# psxpwr.net
KiCad netlist of a schematic drawn in EAGLE
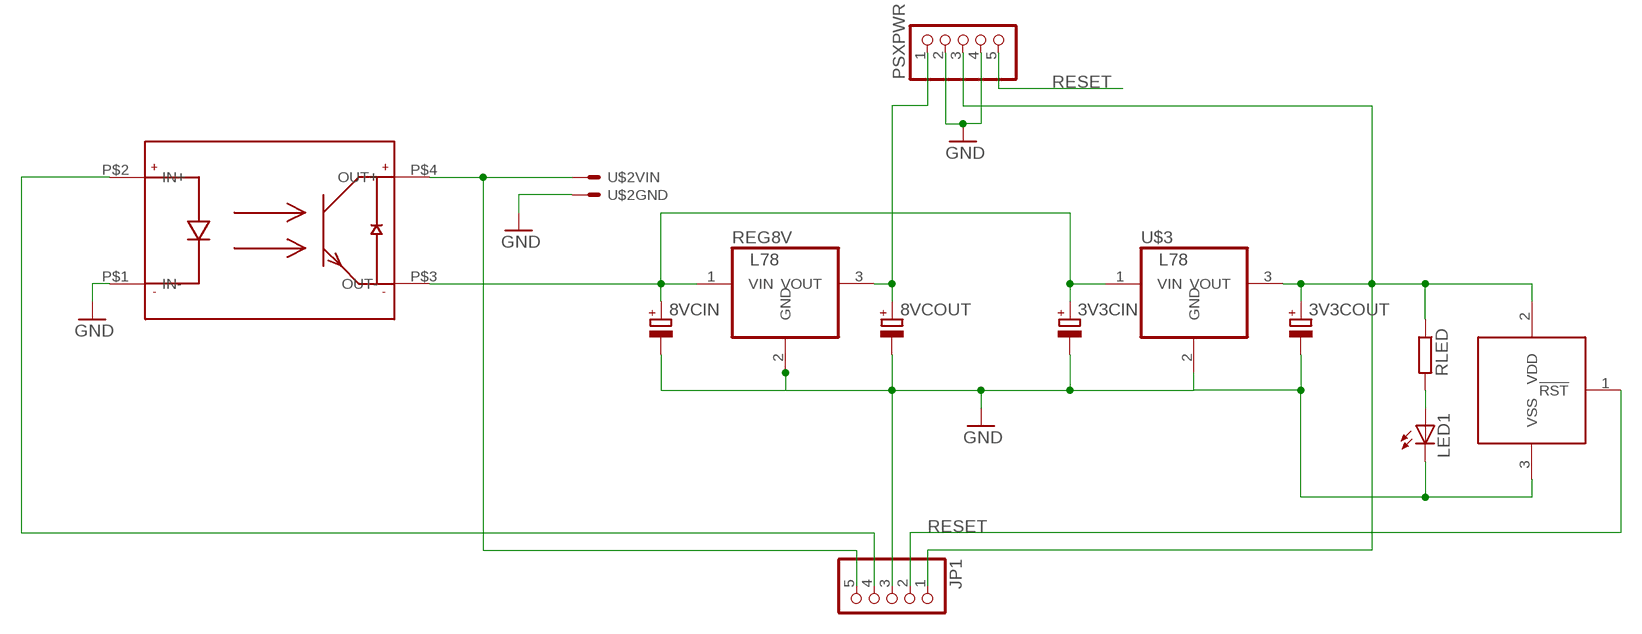
[diagram p0: schematic, sheet 1]

(export (version "E")
  (design (tool "Eeschema 10.0.6"))
  (components
    (comp (ref "3V3CIN")
      (value "CPOL-EUE2.5-6")
      (footprint "eagle-import:E2,5-6")
      (libsource (lib "eagle-import") (part "CPOL-EUE2.5-6"))
    )
    (comp (ref "3V3COUT")
      (value "CPOL-EUE2.5-6")
      (footprint "eagle-import:E2,5-6")
      (libsource (lib "eagle-import") (part "CPOL-EUE2.5-6"))
    )
    (comp (ref "8VCIN")
      (value "CPOL-EUE2.5-6")
      (footprint "eagle-import:E2,5-6")
      (libsource (lib "eagle-import") (part "CPOL-EUE2.5-6"))
    )
    (comp (ref "8VCOUT")
      (value "CPOL-EUE2.5-6")
      (footprint "eagle-import:E2,5-6")
      (libsource (lib "eagle-import") (part "CPOL-EUE2.5-6"))
    )
    (comp (ref "JP1")
      (value "PINHD-1X5")
      (footprint "eagle-import:1X05")
      (libsource (lib "eagle-import") (part "PINHD-1X5"))
    )
    (comp (ref "LED1")
      (value "LED3MM")
      (footprint "eagle-import:LED3MM")
      (libsource (lib "eagle-import") (part "LED3MM"))
    )
    (comp (ref "PSXPWR")
      (value "PINHD-1X5")
      (footprint "eagle-import:1X05")
      (libsource (lib "eagle-import") (part "PINHD-1X5"))
    )
    (comp (ref "REG8V")
      (value "L78")
      (footprint "eagle-import:TO-220-HEATSINK")
      (libsource (lib "eagle-import") (part "L78"))
    )
    (comp (ref "RESET")
      (value "MCP100V3")
      (footprint "eagle-import:TO92-EBC-OVAL")
      (libsource (lib "eagle-import") (part "MCP100V3"))
    )
    (comp (ref "RLED")
      (value "R-EU_0207/2V")
      (footprint "eagle-import:0207_2V")
      (libsource (lib "eagle-import") (part "R-EU_0207/2V"))
    )
    (comp (ref "U$1")
      (value "KF060XD")
      (footprint "eagle-import:KF060XD")
      (libsource (lib "eagle-import") (part "KF060XD"))
    )
    (comp (ref "U$2")
      (value "PWR")
      (footprint "eagle-import:PWR")
      (libsource (lib "eagle-import") (part "PWR"))
    )
    (comp (ref "U$3")
      (value "L78")
      (footprint "eagle-import:TO-220-HEATSINK")
      (libsource (lib "eagle-import") (part "L78"))
    )
  )
  (nets
    (net (code "1") (name "/RESET") (class "Default")
      (node (ref "JP1") (pin "2") (pinfunction "2_2") (pintype "passive"))
      (node (ref "PSXPWR") (pin "5") (pinfunction "5_5") (pintype "passive"))
      (node (ref "RESET") (pin "1") (pinfunction "~{RST}_1") (pintype "bidirectional"))
    )
    (net (code "2") (name "GND") (class "Default")
      (node (ref "3V3CIN") (pin "-") (pinfunction "-_-") (pintype "passive"))
      (node (ref "3V3COUT") (pin "-") (pinfunction "-_-") (pintype "passive"))
      (node (ref "8VCIN") (pin "-") (pinfunction "-_-") (pintype "passive"))
      (node (ref "8VCOUT") (pin "-") (pinfunction "-_-") (pintype "passive"))
      (node (ref "JP1") (pin "3") (pinfunction "3_3") (pintype "passive"))
      (node (ref "LED1") (pin "K") (pinfunction "C_K") (pintype "passive"))
      (node (ref "PSXPWR") (pin "2") (pinfunction "2_2") (pintype "passive"))
      (node (ref "PSXPWR") (pin "4") (pinfunction "4_4") (pintype "passive"))
      (node (ref "REG8V") (pin "2") (pinfunction "GND_2") (pintype "power_in"))
      (node (ref "RESET") (pin "3") (pinfunction "VSS_3") (pintype "bidirectional"))
      (node (ref "U$1") (pin "P$1") (pinfunction "IN-_P$1") (pintype "bidirectional"))
      (node (ref "U$2") (pin "P$1") (pinfunction "S_P$1") (pintype "passive"))
      (node (ref "U$3") (pin "2") (pinfunction "GND_2") (pintype "power_in"))
    )
    (net (code "3") (name "Net-(LED1-PadA)") (class "Default")
      (node (ref "LED1") (pin "A") (pinfunction "A_A") (pintype "passive"))
      (node (ref "RLED") (pin "2") (pinfunction "2_2") (pintype "passive"))
    )
    (net (code "4") (name "Net-(REG8V-VIN)") (class "Default")
      (node (ref "3V3CIN") (pin "+") (pinfunction "+_+") (pintype "passive"))
      (node (ref "8VCIN") (pin "+") (pinfunction "+_+") (pintype "passive"))
      (node (ref "REG8V") (pin "1") (pinfunction "VIN_1") (pintype "input"))
      (node (ref "U$1") (pin "P$3") (pinfunction "OUT-_P$3") (pintype "bidirectional"))
      (node (ref "U$3") (pin "1") (pinfunction "VIN_1") (pintype "input"))
    )
    (net (code "5") (name "Net-(REG8V-VOUT)") (class "Default")
      (node (ref "8VCOUT") (pin "+") (pinfunction "+_+") (pintype "passive"))
      (node (ref "PSXPWR") (pin "1") (pinfunction "1_1") (pintype "passive"))
      (node (ref "REG8V") (pin "3") (pinfunction "VOUT_3") (pintype "output"))
    )
    (net (code "6") (name "Net-(RESET-VDD)") (class "Default")
      (node (ref "3V3COUT") (pin "+") (pinfunction "+_+") (pintype "passive"))
      (node (ref "JP1") (pin "1") (pinfunction "1_1") (pintype "passive"))
      (node (ref "PSXPWR") (pin "3") (pinfunction "3_3") (pintype "passive"))
      (node (ref "RESET") (pin "2") (pinfunction "VDD_2") (pintype "bidirectional"))
      (node (ref "RLED") (pin "1") (pinfunction "1_1") (pintype "passive"))
      (node (ref "U$3") (pin "3") (pinfunction "VOUT_3") (pintype "output"))
    )
    (net (code "7") (name "Net-(U$1-IN+)") (class "Default")
      (node (ref "JP1") (pin "4") (pinfunction "4_4") (pintype "passive"))
      (node (ref "U$1") (pin "P$2") (pinfunction "IN+_P$2") (pintype "bidirectional"))
    )
    (net (code "8") (name "Net-(U$1-OUT+)") (class "Default")
      (node (ref "JP1") (pin "5") (pinfunction "5_5") (pintype "passive"))
      (node (ref "U$1") (pin "P$4") (pinfunction "OUT+_P$4") (pintype "bidirectional"))
      (node (ref "U$2") (pin "P$2") (pinfunction "S_P$2") (pintype "passive"))
    )
  )
)
